# board_rev_1.net
KiCad netlist of a schematic drawn in EAGLE
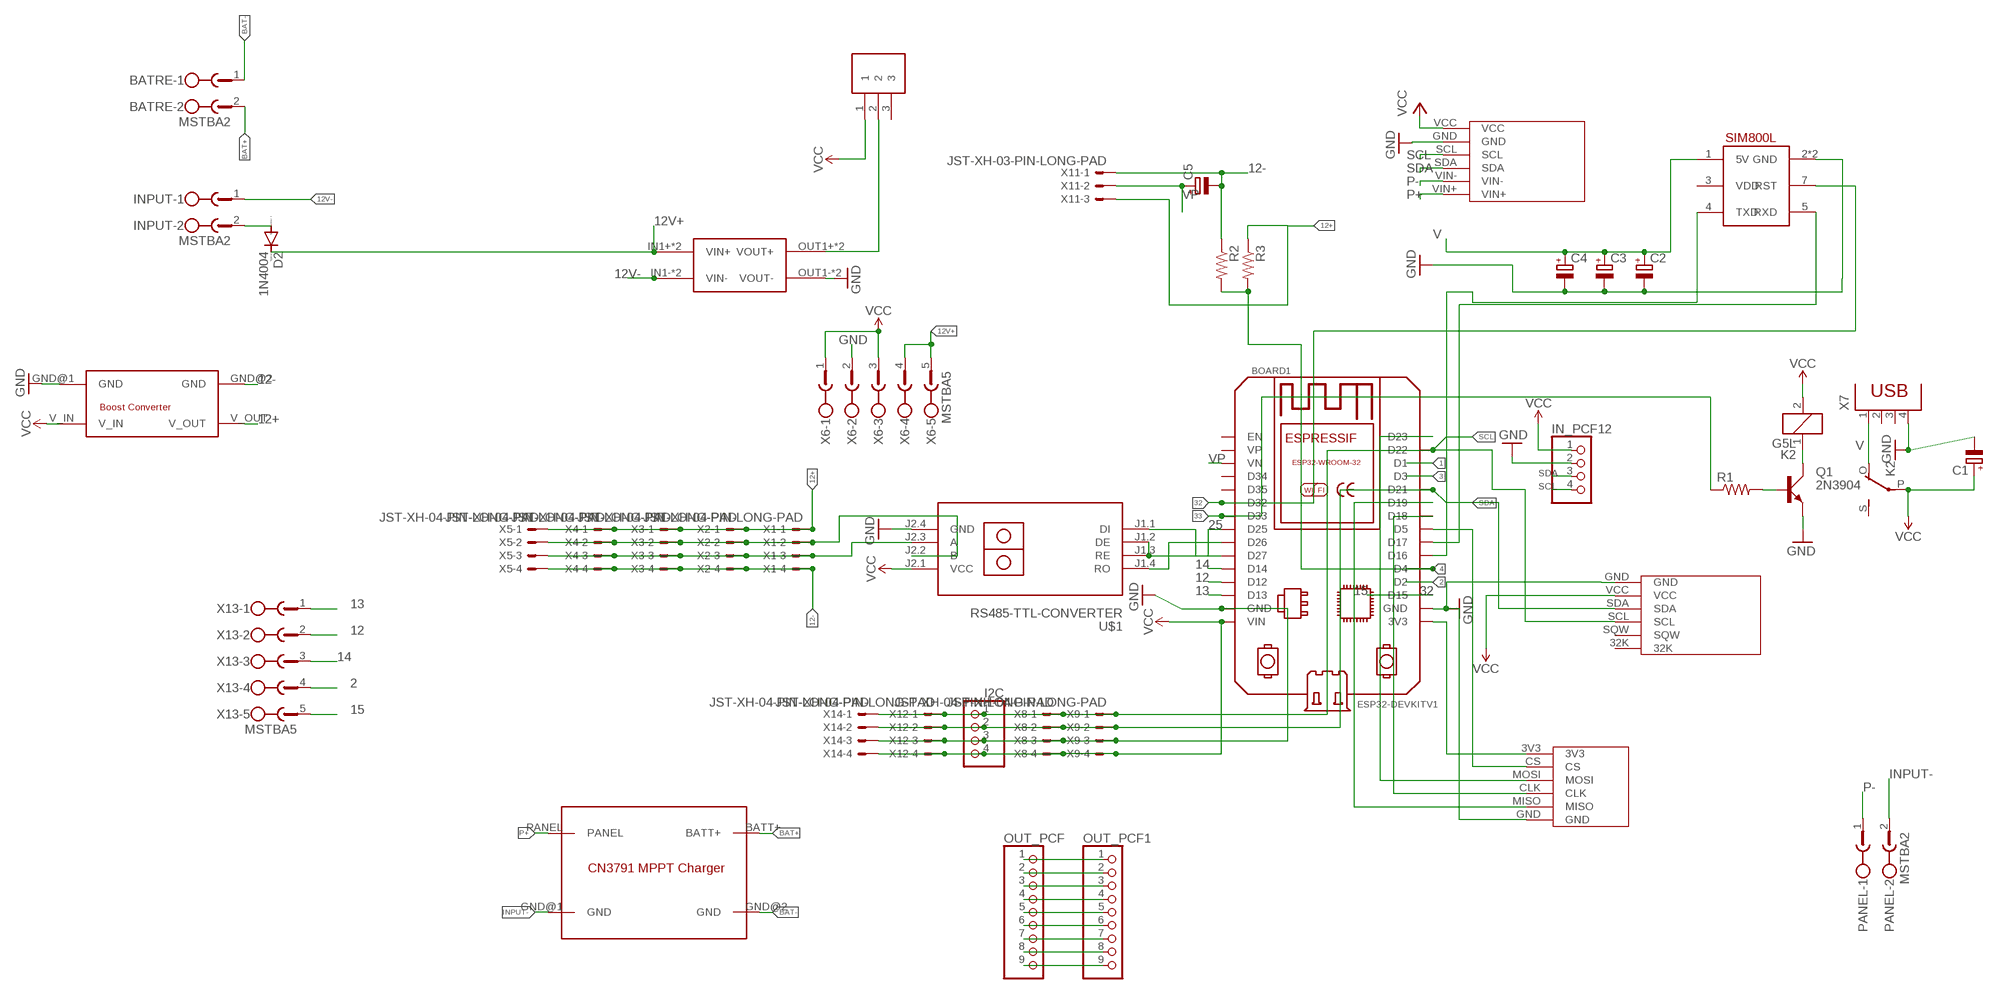
[diagram p0: schematic, sheet 1]

(export (version "E")
  (design (tool "Eeschema 10.0.6"))
  (components
    (comp (ref "BATRE")
      (value "MSTBA2")
      (footprint "eagle-import:MSTBA2")
      (fields (field (name "MF") "FARNELL") (field (name "MPN") "1757242"))
      (libsource (lib "eagle-import") (part "MSTBA2"))
    )
    (comp (ref "BOARD1")
      (value "ESP32DEVKITV1")
      (footprint "eagle-import:ESP32-DEVKITV1")
      (libsource (lib "eagle-import") (part "ESP32DEVKITV1"))
    )
    (comp (ref "C1")
      (value "CPOL-EUE2.5-7")
      (footprint "eagle-import:E2,5-7")
      (libsource (lib "eagle-import") (part "CPOL-EUE2.5-7"))
    )
    (comp (ref "C2")
      (value "CPOL-EUE2.5-7")
      (footprint "eagle-import:E2,5-7")
      (libsource (lib "eagle-import") (part "CPOL-EUE2.5-7"))
    )
    (comp (ref "C3")
      (value "CPOL-EUE2.5-7")
      (footprint "eagle-import:E2,5-7")
      (libsource (lib "eagle-import") (part "CPOL-EUE2.5-7"))
    )
    (comp (ref "C4")
      (value "CPOL-EUE2.5-7")
      (footprint "eagle-import:E2,5-7")
      (libsource (lib "eagle-import") (part "CPOL-EUE2.5-7"))
    )
    (comp (ref "C5")
      (value "CPOL-EUE2.5-7")
      (footprint "eagle-import:E2,5-7")
      (libsource (lib "eagle-import") (part "CPOL-EUE2.5-7"))
    )
    (comp (ref "D2")
      (value "1N4004")
      (footprint "eagle-import:DO41-10")
      (libsource (lib "eagle-import") (part "1N4004"))
    )
    (comp (ref "I2C")
      (value "PINHD-1X4")
      (footprint "eagle-import:1X04")
      (libsource (lib "eagle-import") (part "PINHD-1X4"))
    )
    (comp (ref "INPUT")
      (value "MSTBA2")
      (footprint "eagle-import:MSTBA2")
      (fields (field (name "MF") "FARNELL") (field (name "MPN") "1757242"))
      (libsource (lib "eagle-import") (part "MSTBA2"))
    )
    (comp (ref "IN_PCF12")
      (value "PINHD-1X4")
      (footprint "eagle-import:1X04")
      (libsource (lib "eagle-import") (part "pinhead_325_PINHD-1X4"))
    )
    (comp (ref "K2")
      (value "G5L")
      (footprint "eagle-import:G5LE")
      (libsource (lib "eagle-import") (part "G5L"))
    )
    (comp (ref "OUT_PCF")
      (value "PINHD-1X9")
      (footprint "eagle-import:1X09")
      (libsource (lib "eagle-import") (part "PINHD-1X9"))
    )
    (comp (ref "OUT_PCF1")
      (value "PINHD-1X9")
      (footprint "eagle-import:1X09")
      (libsource (lib "eagle-import") (part "PINHD-1X9"))
    )
    (comp (ref "PANEL")
      (value "MSTBA2")
      (footprint "eagle-import:MSTBA2")
      (fields (field (name "MF") "FARNELL") (field (name "MPN") "1757242"))
      (libsource (lib "eagle-import") (part "MSTBA2"))
    )
    (comp (ref "Q1")
      (value "2N3904")
      (footprint "eagle-import:TO92D")
      (libsource (lib "eagle-import") (part "2N3904"))
    )
    (comp (ref "R1")
      (value "R-US_0204/7")
      (footprint "eagle-import:0204_7")
      (libsource (lib "eagle-import") (part "R-US_0204/7"))
    )
    (comp (ref "R2")
      (value "R-US_0204/7")
      (footprint "eagle-import:0204_7")
      (libsource (lib "eagle-import") (part "R-US_0204/7"))
    )
    (comp (ref "R3")
      (value "R-US_0204/7")
      (footprint "eagle-import:0204_7")
      (libsource (lib "eagle-import") (part "R-US_0204/7"))
    )
    (comp (ref "SW1")
      (value "SS12D10")
      (footprint "eagle-import:SS12D10")
      (libsource (lib "eagle-import") (part "SS12D10"))
    )
    (comp (ref "U$1")
      (value "RS485-TTL-CONVERTER")
      (footprint "eagle-import:RS485-TTL-CONVERTER")
      (libsource (lib "eagle-import") (part "RS485-TTL-CONVERTER"))
    )
    (comp (ref "U$2")
      (value "CN3791_MTTP_LIPO_SOLAR_CHARGER")
      (footprint "eagle-import:CN3791_MPPT_LIPO_SOLAR_CHARGER")
      (libsource (lib "eagle-import") (part "CN3791_MTTP_LIPO_SOLAR_CHARGER"))
    )
    (comp (ref "U$3")
      (value "MP1584")
      (footprint "eagle-import:DC-BRICK")
      (libsource (lib "eagle-import") (part "MP1584"))
    )
    (comp (ref "U$4")
      (value "SIM800L")
      (footprint "eagle-import:SIP")
      (libsource (lib "eagle-import") (part "SIM800L"))
    )
    (comp (ref "U$5")
      (value "ICSA004A_BOOST_MODULE")
      (footprint "eagle-import:ICSA004A_BOOST_MODULE")
      (libsource (lib "eagle-import") (part "ICSA004A_BOOST_MODULE"))
    )
    (comp (ref "U$6")
      (value "DS3231")
      (footprint "eagle-import:DS3231")
      (libsource (lib "eagle-import") (part "DS3231"))
    )
    (comp (ref "U$7")
      (value "MICROSD3V3")
      (footprint "eagle-import:MICROSD3V3")
      (libsource (lib "eagle-import") (part "MICROSD3V3"))
    )
    (comp (ref "U$8")
      (value "INA219")
      (footprint "eagle-import:INA219")
      (libsource (lib "eagle-import") (part "INA219"))
    )
    (comp (ref "X1")
      (value "JST-XH-04-PIN-LONG-PAD")
      (footprint "eagle-import:JST-XH-04-PACKAGE-LONG-PAD")
      (libsource (lib "eagle-import") (part "JST-XH-04-PIN-LONG-PAD"))
    )
    (comp (ref "X2")
      (value "JST-XH-04-PIN-LONG-PAD")
      (footprint "eagle-import:JST-XH-04-PACKAGE-LONG-PAD")
      (libsource (lib "eagle-import") (part "JST-XH-04-PIN-LONG-PAD"))
    )
    (comp (ref "X3")
      (value "JST-XH-04-PIN-LONG-PAD")
      (footprint "eagle-import:JST-XH-04-PACKAGE-LONG-PAD")
      (libsource (lib "eagle-import") (part "JST-XH-04-PIN-LONG-PAD"))
    )
    (comp (ref "X4")
      (value "JST-XH-04-PIN-LONG-PAD")
      (footprint "eagle-import:JST-XH-04-PACKAGE-LONG-PAD")
      (libsource (lib "eagle-import") (part "JST-XH-04-PIN-LONG-PAD"))
    )
    (comp (ref "X5")
      (value "JST-XH-04-PIN-LONG-PAD")
      (footprint "eagle-import:JST-XH-04-PACKAGE-LONG-PAD")
      (libsource (lib "eagle-import") (part "JST-XH-04-PIN-LONG-PAD"))
    )
    (comp (ref "X6")
      (value "MSTBA5")
      (footprint "eagle-import:MSTBA5")
      (fields (field (name "MPN") "1757271"))
      (libsource (lib "eagle-import") (part "MSTBA5"))
    )
    (comp (ref "X7")
      (value "PN87520")
      (footprint "eagle-import:PN87520")
      (libsource (lib "eagle-import") (part "PN87520"))
    )
    (comp (ref "X8")
      (value "JST-XH-04-PIN-LONG-PAD")
      (footprint "eagle-import:JST-XH-04-PACKAGE-LONG-PAD")
      (libsource (lib "eagle-import") (part "JST-XH-04-PIN-LONG-PAD"))
    )
    (comp (ref "X9")
      (value "JST-XH-04-PIN-LONG-PAD")
      (footprint "eagle-import:JST-XH-04-PACKAGE-LONG-PAD")
      (libsource (lib "eagle-import") (part "JST-XH-04-PIN-LONG-PAD"))
    )
    (comp (ref "X11")
      (value "JST-XH-03-PIN-LONG-PAD")
      (footprint "eagle-import:JST-XH-03-PACKAGE-LONG-PAD")
      (libsource (lib "eagle-import") (part "JST-XH-03-PIN-LONG-PAD"))
    )
    (comp (ref "X12")
      (value "JST-XH-04-PIN-LONG-PAD")
      (footprint "eagle-import:JST-XH-04-PACKAGE-LONG-PAD")
      (libsource (lib "eagle-import") (part "JST-XH-04-PIN-LONG-PAD"))
    )
    (comp (ref "X13")
      (value "MSTBA5")
      (footprint "eagle-import:MSTBA5")
      (fields (field (name "MPN") "1757271"))
      (libsource (lib "eagle-import") (part "MSTBA5"))
    )
    (comp (ref "X14")
      (value "JST-XH-04-PIN-LONG-PAD")
      (footprint "eagle-import:JST-XH-04-PACKAGE-LONG-PAD")
      (libsource (lib "eagle-import") (part "JST-XH-04-PIN-LONG-PAD"))
    )
  )
  (nets
    (net (code "1") (name "/12") (class "Default")
      (node (ref "BOARD1") (pin "D12") (pinfunction "D12_D12") (pintype "bidirectional"))
      (node (ref "X13") (pin "2") (pinfunction "1_2") (pintype "passive"))
    )
    (net (code "2") (name "/13") (class "Default")
      (node (ref "BOARD1") (pin "D13") (pinfunction "D13_D13") (pintype "bidirectional"))
      (node (ref "X13") (pin "1") (pinfunction "1_1") (pintype "passive"))
    )
    (net (code "3") (name "/14") (class "Default")
      (node (ref "BOARD1") (pin "D14") (pinfunction "D14_D14") (pintype "bidirectional"))
      (node (ref "X13") (pin "3") (pinfunction "1_3") (pintype "passive"))
    )
    (net (code "4") (name "/15") (class "Default")
      (node (ref "BOARD1") (pin "D15") (pinfunction "D15_D15") (pintype "bidirectional"))
      (node (ref "X13") (pin "5") (pinfunction "1_5") (pintype "passive"))
    )
    (net (code "5") (name "/25") (class "Default")
      (node (ref "BOARD1") (pin "D25") (pinfunction "D25_D25") (pintype "bidirectional"))
      (node (ref "U$1") (pin "J1.2") (pinfunction "DE_J1.2") (pintype "passive"))
      (node (ref "U$1") (pin "J1.3") (pinfunction "RE_J1.3") (pintype "passive"))
    )
    (net (code "6") (name "/P-") (class "Default")
      (node (ref "PANEL") (pin "1") (pinfunction "1_1") (pintype "passive"))
      (node (ref "U$8") (pin "VIN-") (pinfunction "VIN-_VIN-") (pintype "bidirectional"))
    )
    (net (code "7") (name "/V") (class "Default")
      (node (ref "C2") (pin "+") (pinfunction "+_+") (pintype "passive"))
      (node (ref "C3") (pin "+") (pinfunction "+_+") (pintype "passive"))
      (node (ref "C4") (pin "+") (pinfunction "+_+") (pintype "passive"))
      (node (ref "K2") (pin "O") (pinfunction "O_O") (pintype "passive"))
      (node (ref "U$4") (pin "1") (pinfunction "5V_1") (pintype "bidirectional"))
      (node (ref "X7") (pin "1") (pinfunction "1_1") (pintype "passive"))
    )
    (net (code "8") (name "/VP") (class "Default")
      (node (ref "BOARD1") (pin "VN") (pinfunction "VN_VN") (pintype "bidirectional"))
      (node (ref "C5") (pin "+") (pinfunction "+_+") (pintype "passive"))
      (node (ref "X11") (pin "2") (pinfunction "S_2") (pintype "passive"))
    )
    (net (code "9") (name "1") (class "Default")
      (node (ref "BOARD1") (pin "D1") (pinfunction "D1_D1") (pintype "bidirectional"))
    )
    (net (code "10") (name "2") (class "Default")
      (node (ref "BOARD1") (pin "D2") (pinfunction "D2_D2") (pintype "bidirectional"))
      (node (ref "X13") (pin "4") (pinfunction "1_4") (pintype "passive"))
    )
    (net (code "11") (name "3") (class "Default")
      (node (ref "BOARD1") (pin "D3") (pinfunction "D3_D3") (pintype "bidirectional"))
    )
    (net (code "12") (name "4") (class "Default")
      (node (ref "BOARD1") (pin "D4") (pinfunction "D4_D4") (pintype "bidirectional"))
      (node (ref "R2") (pin "2") (pinfunction "2_2") (pintype "passive"))
      (node (ref "R3") (pin "2") (pinfunction "2_2") (pintype "passive"))
    )
    (net (code "13") (name "12+") (class "Default")
      (node (ref "R3") (pin "1") (pinfunction "1_1") (pintype "passive"))
      (node (ref "U$5") (pin "V_OUT") (pinfunction "V_OUT_V_OUT") (pintype "output"))
      (node (ref "X1") (pin "1") (pinfunction "S_1") (pintype "passive"))
      (node (ref "X11") (pin "3") (pinfunction "S_3") (pintype "passive"))
      (node (ref "X2") (pin "1") (pinfunction "S_1") (pintype "passive"))
      (node (ref "X3") (pin "1") (pinfunction "S_1") (pintype "passive"))
      (node (ref "X4") (pin "1") (pinfunction "S_1") (pintype "passive"))
      (node (ref "X5") (pin "1") (pinfunction "S_1") (pintype "passive"))
    )
    (net (code "14") (name "12-") (class "Default")
      (node (ref "C5") (pin "-") (pinfunction "-_-") (pintype "passive"))
      (node (ref "R2") (pin "1") (pinfunction "1_1") (pintype "passive"))
      (node (ref "U$5") (pin "GND@2") (pinfunction "GND_GND@2") (pintype "power_in"))
      (node (ref "X1") (pin "4") (pinfunction "S_4") (pintype "passive"))
      (node (ref "X11") (pin "1") (pinfunction "S_1") (pintype "passive"))
      (node (ref "X2") (pin "4") (pinfunction "S_4") (pintype "passive"))
      (node (ref "X3") (pin "4") (pinfunction "S_4") (pintype "passive"))
      (node (ref "X4") (pin "4") (pinfunction "S_4") (pintype "passive"))
      (node (ref "X5") (pin "4") (pinfunction "S_4") (pintype "passive"))
    )
    (net (code "15") (name "12V+") (class "Default")
      (node (ref "D2") (pin "C") (pinfunction "C_C") (pintype "passive"))
      (node (ref "U$3") (pin "IN1+") (pinfunction "VIN+_IN1+") (pintype "input"))
      (node (ref "U$3") (pin "IN2+") (pinfunction "VIN+_IN2+") (pintype "input"))
      (node (ref "X6") (pin "4") (pinfunction "1_4") (pintype "passive"))
      (node (ref "X6") (pin "5") (pinfunction "1_5") (pintype "passive"))
    )
    (net (code "16") (name "12V-") (class "Default")
      (node (ref "INPUT") (pin "1") (pinfunction "1_1") (pintype "passive"))
      (node (ref "U$3") (pin "IN1-") (pinfunction "VIN-_IN1-") (pintype "input"))
      (node (ref "U$3") (pin "IN2-") (pinfunction "VIN-_IN2-") (pintype "input"))
    )
    (net (code "17") (name "32") (class "Default")
      (node (ref "BOARD1") (pin "D32") (pinfunction "D32_D32") (pintype "bidirectional"))
      (node (ref "U$4") (pin "7") (pinfunction "RST_7") (pintype "bidirectional"))
    )
    (net (code "18") (name "33") (class "Default")
      (node (ref "BOARD1") (pin "D33") (pinfunction "D33_D33") (pintype "bidirectional"))
      (node (ref "R1") (pin "1") (pinfunction "1_1") (pintype "passive"))
    )
    (net (code "19") (name "BAT+") (class "Default")
      (node (ref "BATRE") (pin "2") (pinfunction "1_2") (pintype "passive"))
      (node (ref "U$2") (pin "BATT+") (pinfunction "BATT+_BATT+") (pintype "bidirectional"))
    )
    (net (code "20") (name "BAT-") (class "Default")
      (node (ref "BATRE") (pin "1") (pinfunction "1_1") (pintype "passive"))
      (node (ref "U$2") (pin "GND@2") (pinfunction "GND_GND@2") (pintype "bidirectional"))
    )
    (net (code "21") (name "GND") (class "Default")
      (node (ref "BOARD1") (pin "GND") (pinfunction "GND_GND") (pintype "bidirectional"))
      (node (ref "BOARD1") (pin "GND@1") (pinfunction "GND_GND@1") (pintype "bidirectional"))
      (node (ref "C1") (pin "-") (pinfunction "-_-") (pintype "passive"))
      (node (ref "C2") (pin "-") (pinfunction "-_-") (pintype "passive"))
      (node (ref "C3") (pin "-") (pinfunction "-_-") (pintype "passive"))
      (node (ref "C4") (pin "-") (pinfunction "-_-") (pintype "passive"))
      (node (ref "I2C") (pin "3") (pinfunction "3_3") (pintype "passive"))
      (node (ref "IN_PCF12") (pin "2") (pinfunction "2_2") (pintype "passive"))
      (node (ref "Q1") (pin "E") (pinfunction "E_E") (pintype "passive"))
      (node (ref "U$1") (pin "J2.4") (pinfunction "GND_J2.4") (pintype "power_in"))
      (node (ref "U$3") (pin "OUT1-") (pinfunction "VOUT-_OUT1-") (pintype "output"))
      (node (ref "U$3") (pin "OUT2-") (pinfunction "VOUT-_OUT2-") (pintype "output"))
      (node (ref "U$4") (pin "2") (pinfunction "GND_2") (pintype "bidirectional"))
      (node (ref "U$4") (pin "6") (pinfunction "GND_6") (pintype "bidirectional"))
      (node (ref "U$5") (pin "GND@1") (pinfunction "GND_GND@1") (pintype "power_in"))
      (node (ref "U$6") (pin "GND") (pinfunction "GND_GND") (pintype "bidirectional"))
      (node (ref "U$7") (pin "GND") (pinfunction "GND_GND") (pintype "bidirectional"))
      (node (ref "U$8") (pin "GND") (pinfunction "GND_GND") (pintype "bidirectional"))
      (node (ref "X12") (pin "3") (pinfunction "S_3") (pintype "passive"))
      (node (ref "X14") (pin "3") (pinfunction "S_3") (pintype "passive"))
      (node (ref "X6") (pin "2") (pinfunction "1_2") (pintype "passive"))
      (node (ref "X7") (pin "4") (pinfunction "4_4") (pintype "passive"))
      (node (ref "X8") (pin "3") (pinfunction "S_3") (pintype "passive"))
      (node (ref "X9") (pin "3") (pinfunction "S_3") (pintype "passive"))
    )
    (net (code "22") (name "INPUT-") (class "Default")
      (node (ref "PANEL") (pin "2") (pinfunction "1_2") (pintype "passive"))
      (node (ref "U$2") (pin "GND@1") (pinfunction "GND_GND@1") (pintype "bidirectional"))
    )
    (net (code "23") (name "Net-(BOARD1-Pad3V3)") (class "Default")
      (node (ref "BOARD1") (pin "3V3") (pinfunction "3V3_3V3") (pintype "bidirectional"))
      (node (ref "U$7") (pin "3V3") (pinfunction "3V3_3V3") (pintype "bidirectional"))
    )
    (net (code "24") (name "Net-(BOARD1-PadD5)") (class "Default")
      (node (ref "BOARD1") (pin "D5") (pinfunction "D5_D5") (pintype "bidirectional"))
      (node (ref "U$7") (pin "CS") (pinfunction "CS_CS") (pintype "bidirectional"))
    )
    (net (code "25") (name "Net-(BOARD1-PadD18)") (class "Default")
      (node (ref "BOARD1") (pin "D18") (pinfunction "D18_D18") (pintype "bidirectional"))
      (node (ref "U$7") (pin "CLK") (pinfunction "CLK_CLK") (pintype "bidirectional"))
    )
    (net (code "26") (name "Net-(BOARD1-PadD19)") (class "Default")
      (node (ref "BOARD1") (pin "D19") (pinfunction "D19_D19") (pintype "bidirectional"))
      (node (ref "U$7") (pin "MISO") (pinfunction "MISO_MISO") (pintype "bidirectional"))
    )
    (net (code "27") (name "Net-(BOARD1-PadD23)") (class "Default")
      (node (ref "BOARD1") (pin "D23") (pinfunction "D23_D23") (pintype "bidirectional"))
      (node (ref "U$7") (pin "MOSI") (pinfunction "MOSI_MOSI") (pintype "bidirectional"))
    )
    (net (code "28") (name "Net-(INPUTB-1)") (class "Default")
      (node (ref "D2") (pin "A") (pinfunction "A_A") (pintype "passive"))
      (node (ref "INPUT") (pin "2") (pinfunction "1_2") (pintype "passive"))
    )
    (net (code "29") (name "Net-(K2-Pad1)") (class "Default")
      (node (ref "K2") (pin "1") (pinfunction "1_1") (pintype "passive"))
      (node (ref "Q1") (pin "C") (pinfunction "C_C") (pintype "passive"))
    )
    (net (code "30") (name "Net-(OUT_PCF-Pad1)") (class "Default")
      (node (ref "OUT_PCF") (pin "1") (pinfunction "1_1") (pintype "passive"))
      (node (ref "OUT_PCF1") (pin "1") (pinfunction "1_1") (pintype "passive"))
    )
    (net (code "31") (name "Net-(OUT_PCF-Pad2)") (class "Default")
      (node (ref "OUT_PCF") (pin "2") (pinfunction "2_2") (pintype "passive"))
      (node (ref "OUT_PCF1") (pin "2") (pinfunction "2_2") (pintype "passive"))
    )
    (net (code "32") (name "Net-(OUT_PCF-Pad3)") (class "Default")
      (node (ref "OUT_PCF") (pin "3") (pinfunction "3_3") (pintype "passive"))
      (node (ref "OUT_PCF1") (pin "3") (pinfunction "3_3") (pintype "passive"))
    )
    (net (code "33") (name "Net-(OUT_PCF-Pad4)") (class "Default")
      (node (ref "OUT_PCF") (pin "4") (pinfunction "4_4") (pintype "passive"))
      (node (ref "OUT_PCF1") (pin "4") (pinfunction "4_4") (pintype "passive"))
    )
    (net (code "34") (name "Net-(OUT_PCF-Pad5)") (class "Default")
      (node (ref "OUT_PCF") (pin "5") (pinfunction "5_5") (pintype "passive"))
      (node (ref "OUT_PCF1") (pin "5") (pinfunction "5_5") (pintype "passive"))
    )
    (net (code "35") (name "Net-(OUT_PCF-Pad6)") (class "Default")
      (node (ref "OUT_PCF") (pin "6") (pinfunction "6_6") (pintype "passive"))
      (node (ref "OUT_PCF1") (pin "6") (pinfunction "6_6") (pintype "passive"))
    )
    (net (code "36") (name "Net-(OUT_PCF-Pad7)") (class "Default")
      (node (ref "OUT_PCF") (pin "7") (pinfunction "7_7") (pintype "passive"))
      (node (ref "OUT_PCF1") (pin "7") (pinfunction "7_7") (pintype "passive"))
    )
    (net (code "37") (name "Net-(OUT_PCF-Pad8)") (class "Default")
      (node (ref "OUT_PCF") (pin "8") (pinfunction "8_8") (pintype "passive"))
      (node (ref "OUT_PCF1") (pin "8") (pinfunction "8_8") (pintype "passive"))
    )
    (net (code "38") (name "Net-(OUT_PCF-Pad9)") (class "Default")
      (node (ref "OUT_PCF") (pin "9") (pinfunction "9_9") (pintype "passive"))
      (node (ref "OUT_PCF1") (pin "9") (pinfunction "9_9") (pintype "passive"))
    )
    (net (code "39") (name "Net-(Q1-PadB)") (class "Default")
      (node (ref "Q1") (pin "B") (pinfunction "B_B") (pintype "passive"))
      (node (ref "R1") (pin "2") (pinfunction "2_2") (pintype "passive"))
    )
    (net (code "40") (name "Net-(SW1-Pad2)") (class "Default")
      (node (ref "SW1") (pin "2") (pinfunction "2_2") (pintype "bidirectional"))
      (node (ref "U$3") (pin "OUT1+") (pinfunction "VOUT+_OUT1+") (pintype "output"))
      (node (ref "U$3") (pin "OUT2+") (pinfunction "VOUT+_OUT2+") (pintype "output"))
    )
    (net (code "41") (name "Net-(U$1-A)") (class "Default")
      (node (ref "U$1") (pin "J2.3") (pinfunction "A_J2.3") (pintype "passive"))
      (node (ref "X1") (pin "3") (pinfunction "S_3") (pintype "passive"))
      (node (ref "X2") (pin "3") (pinfunction "S_3") (pintype "passive"))
      (node (ref "X3") (pin "3") (pinfunction "S_3") (pintype "passive"))
      (node (ref "X4") (pin "3") (pinfunction "S_3") (pintype "passive"))
      (node (ref "X5") (pin "3") (pinfunction "S_3") (pintype "passive"))
    )
    (net (code "42") (name "Net-(U$1-B)") (class "Default")
      (node (ref "U$1") (pin "J2.2") (pinfunction "B_J2.2") (pintype "passive"))
      (node (ref "X1") (pin "2") (pinfunction "S_2") (pintype "passive"))
      (node (ref "X2") (pin "2") (pinfunction "S_2") (pintype "passive"))
      (node (ref "X3") (pin "2") (pinfunction "S_2") (pintype "passive"))
      (node (ref "X4") (pin "2") (pinfunction "S_2") (pintype "passive"))
      (node (ref "X5") (pin "2") (pinfunction "S_2") (pintype "passive"))
    )
    (net (code "43") (name "Net-(U$1-DI)") (class "Default")
      (node (ref "BOARD1") (pin "D27") (pinfunction "D27_D27") (pintype "bidirectional"))
      (node (ref "U$1") (pin "J1.1") (pinfunction "DI_J1.1") (pintype "passive"))
    )
    (net (code "44") (name "Net-(U$1-RO)") (class "Default")
      (node (ref "BOARD1") (pin "D26") (pinfunction "D26_D26") (pintype "bidirectional"))
      (node (ref "U$1") (pin "J1.4") (pinfunction "RO_J1.4") (pintype "passive"))
    )
    (net (code "45") (name "Net-(U$4-RXD)") (class "Default")
      (node (ref "BOARD1") (pin "D17") (pinfunction "D17_D17") (pintype "bidirectional"))
      (node (ref "U$4") (pin "5") (pinfunction "RXD_5") (pintype "bidirectional"))
    )
    (net (code "46") (name "Net-(U$4-TXD)") (class "Default")
      (node (ref "BOARD1") (pin "D16") (pinfunction "D16_D16") (pintype "bidirectional"))
      (node (ref "U$4") (pin "4") (pinfunction "TXD_4") (pintype "bidirectional"))
    )
    (net (code "47") (name "P+") (class "Default")
      (node (ref "U$2") (pin "PANEL") (pinfunction "PANEL_PANEL") (pintype "bidirectional"))
      (node (ref "U$8") (pin "VIN+") (pinfunction "VIN+_VIN+") (pintype "bidirectional"))
    )
    (net (code "48") (name "SCL") (class "Default")
      (node (ref "BOARD1") (pin "D22") (pinfunction "D22_D22") (pintype "bidirectional"))
      (node (ref "I2C") (pin "1") (pinfunction "1_1") (pintype "passive"))
      (node (ref "IN_PCF12") (pin "4") (pinfunction "4_4") (pintype "passive"))
      (node (ref "U$6") (pin "SCL") (pinfunction "SCL_SCL") (pintype "bidirectional"))
      (node (ref "U$8") (pin "SCL") (pinfunction "SCL_SCL") (pintype "bidirectional"))
      (node (ref "X12") (pin "1") (pinfunction "S_1") (pintype "passive"))
      (node (ref "X14") (pin "1") (pinfunction "S_1") (pintype "passive"))
      (node (ref "X8") (pin "1") (pinfunction "S_1") (pintype "passive"))
      (node (ref "X9") (pin "1") (pinfunction "S_1") (pintype "passive"))
    )
    (net (code "49") (name "SDA") (class "Default")
      (node (ref "BOARD1") (pin "D21") (pinfunction "D21_D21") (pintype "bidirectional"))
      (node (ref "I2C") (pin "2") (pinfunction "2_2") (pintype "passive"))
      (node (ref "IN_PCF12") (pin "3") (pinfunction "3_3") (pintype "passive"))
      (node (ref "U$6") (pin "SDA") (pinfunction "SDA_SDA") (pintype "bidirectional"))
      (node (ref "U$8") (pin "SDA") (pinfunction "SDA_SDA") (pintype "bidirectional"))
      (node (ref "X12") (pin "2") (pinfunction "S_2") (pintype "passive"))
      (node (ref "X14") (pin "2") (pinfunction "S_2") (pintype "passive"))
      (node (ref "X8") (pin "2") (pinfunction "S_2") (pintype "passive"))
      (node (ref "X9") (pin "2") (pinfunction "S_2") (pintype "passive"))
    )
    (net (code "50") (name "VCC") (class "Default")
      (node (ref "BOARD1") (pin "VIN") (pinfunction "VIN_VIN") (pintype "bidirectional"))
      (node (ref "C1") (pin "+") (pinfunction "+_+") (pintype "passive"))
      (node (ref "I2C") (pin "4") (pinfunction "4_4") (pintype "passive"))
      (node (ref "IN_PCF12") (pin "1") (pinfunction "1_1") (pintype "passive"))
      (node (ref "K2") (pin "2") (pinfunction "2_2") (pintype "passive"))
      (node (ref "K2") (pin "P") (pinfunction "P_P") (pintype "passive"))
      (node (ref "SW1") (pin "1") (pinfunction "1_1") (pintype "bidirectional"))
      (node (ref "U$1") (pin "J2.1") (pinfunction "VCC_J2.1") (pintype "power_in"))
      (node (ref "U$5") (pin "V_IN") (pinfunction "V_IN_V_IN") (pintype "power_in"))
      (node (ref "U$6") (pin "VCC") (pinfunction "VCC_VCC") (pintype "bidirectional"))
      (node (ref "U$8") (pin "VCC") (pinfunction "VCC_VCC") (pintype "bidirectional"))
      (node (ref "X12") (pin "4") (pinfunction "S_4") (pintype "passive"))
      (node (ref "X14") (pin "4") (pinfunction "S_4") (pintype "passive"))
      (node (ref "X6") (pin "1") (pinfunction "1_1") (pintype "passive"))
      (node (ref "X6") (pin "3") (pinfunction "1_3") (pintype "passive"))
      (node (ref "X8") (pin "4") (pinfunction "S_4") (pintype "passive"))
      (node (ref "X9") (pin "4") (pinfunction "S_4") (pintype "passive"))
    )
    (net (code "51") (name "unconnected-(BOARD1-PadD34)") (class "Default")
      (node (ref "BOARD1") (pin "D34") (pinfunction "D34_D34") (pintype "bidirectional"))
    )
    (net (code "52") (name "unconnected-(BOARD1-PadD35)") (class "Default")
      (node (ref "BOARD1") (pin "D35") (pinfunction "D35_D35") (pintype "bidirectional"))
    )
    (net (code "53") (name "unconnected-(BOARD1-PadEN)") (class "Default")
      (node (ref "BOARD1") (pin "EN") (pinfunction "EN_EN") (pintype "bidirectional"))
    )
    (net (code "54") (name "unconnected-(BOARD1-PadVP)") (class "Default")
      (node (ref "BOARD1") (pin "VP") (pinfunction "VP_VP") (pintype "bidirectional"))
    )
    (net (code "55") (name "unconnected-(K2-PadS)") (class "Default")
      (node (ref "K2") (pin "S") (pinfunction "S_S") (pintype "passive"))
    )
    (net (code "56") (name "unconnected-(SW1-Pad3)") (class "Default")
      (node (ref "SW1") (pin "3") (pinfunction "3_3") (pintype "bidirectional"))
    )
    (net (code "57") (name "unconnected-(U$4-VDD-Pad3)") (class "Default")
      (node (ref "U$4") (pin "3") (pinfunction "VDD_3") (pintype "bidirectional"))
    )
    (net (code "58") (name "unconnected-(U$6-Pad32K)") (class "Default")
      (node (ref "U$6") (pin "32K") (pinfunction "32K_32K") (pintype "bidirectional"))
    )
    (net (code "59") (name "unconnected-(U$6-PadSQW)") (class "Default")
      (node (ref "U$6") (pin "SQW") (pinfunction "SQW_SQW") (pintype "bidirectional"))
    )
    (net (code "60") (name "unconnected-(X7-Pad2)") (class "Default")
      (node (ref "X7") (pin "2") (pinfunction "2_2") (pintype "passive"))
    )
    (net (code "61") (name "unconnected-(X7-Pad3)") (class "Default")
      (node (ref "X7") (pin "3") (pinfunction "3_3") (pintype "passive"))
    )
  )
)
